# CE842170260_SHEET3.net
KiCad netlist of a schematic drawn in Altium Designer
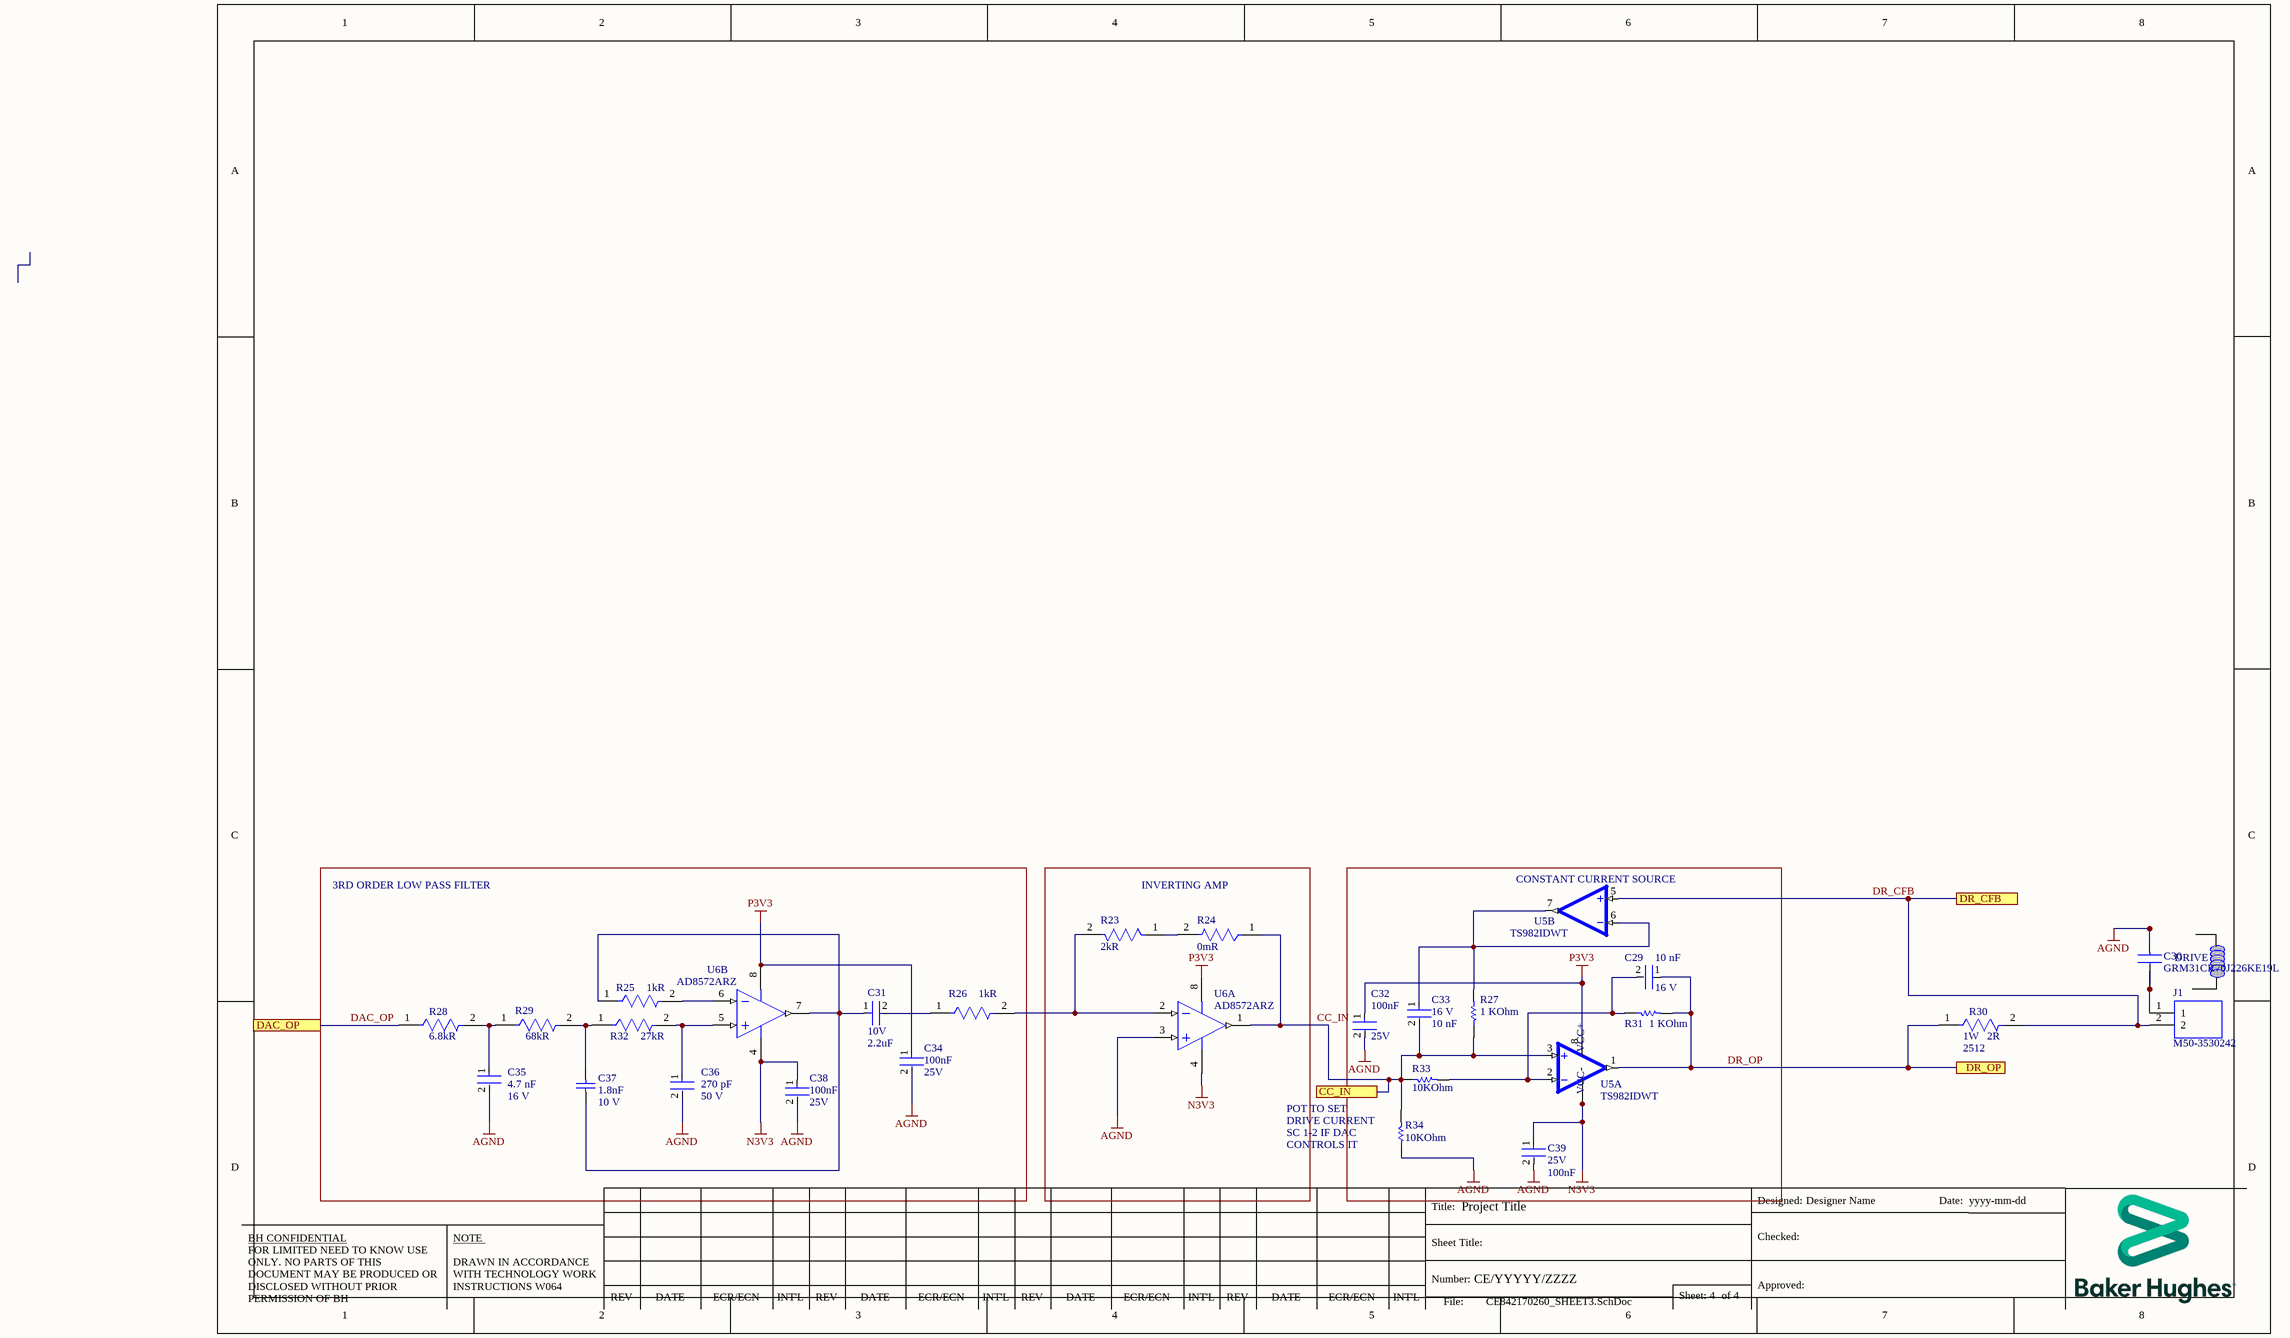
[diagram p0: CE842170260_SHEET3.SchDoc]

(export (version "E")
  (design (tool "Eeschema 10.0.6"))
  (components
    (comp (ref "C29")
      (value "CC0402KRX7R7BB103")
      (footprint "FP-CC0402-MFG")
      (description "CAP CER 10000PF 16V X7R 0402")
      (fields
        (field (name "CAPACITANCE") "10 nF")
        (field (name "TOLERANCE") "0.1")
        (field (name "VOLTAGE RATING") "16 V")
        (field (name "MANUFACTURER") "YAGEO")
      )
      (libsource (lib "Altium Content Vault") (part "11868f565c42a9108669ba33697ecf6"))
    )
    (comp (ref "C30")
      (value "GRM31CR70J226KE19L")
      (footprint "CAPC3216X180N")
      (description "Murata 1206 GRM 22uF Ceramic Multilayer Capacitor, 6.3 V dc, +125C, X7R Dielectric, +/-10% SMD")
      (fields (field (name "MOUSER PART NUMBER") "81-GRM31CR70J226KE9L"))
      (libsource (lib "GRM31CR70J226KE19L") (part "GRM31CR70J226KE19L"))
    )
    (comp (ref "C31")
      (value "CGB3B3X5R1A225M055AB")
      (footprint "FP-CGB3B-IPC_A")
      (description "Multilayer Ceramic Capacitors 2.2uF ±20% 10V X5R SMD 0603")
      (fields
        (field (name "VOLTAGE RATING") "10V")
        (field (name "TOLERANCE") "20%")
        (field (name "CAPACITANCE") "2.2uF")
      )
      (libsource (lib "Altium Content Vault") (part "b4654b650e69147ec39a6b967a45e02"))
    )
    (comp (ref "C32")
      (value "C1005X5R1E104K050BC")
      (footprint "FP-C1005-050-0_05-MFG")
      (description "Multilayer Ceramic Capacitors 100nF ±10% 25V X5R SMD 0402")
      (fields
        (field (name "VOLTAGE RATING (DC)") "25V")
        (field (name "CAPACITANCE") "100nF")
        (field (name "TOLERANCE") "10%")
        (field (name "VOLTAGE") "25V")
      )
      (libsource (lib "Altium Content Vault") (part "b4654b650e69147ec39a6b967a45e02"))
    )
    (comp (ref "C33")
      (value "CC0402KRX7R7BB103")
      (footprint "FP-CC0402-MFG")
      (description "CAP CER 10000PF 16V X7R 0402")
      (fields
        (field (name "CAPACITANCE") "10 nF")
        (field (name "TOLERANCE") "0.1")
        (field (name "VOLTAGE RATING") "16 V")
        (field (name "MANUFACTURER") "YAGEO")
      )
      (libsource (lib "Altium Content Vault") (part "11868f565c42a9108669ba33697ecf6"))
    )
    (comp (ref "C34")
      (value "C1005X5R1E104K050BC")
      (footprint "FP-C1005-050-0_05-MFG")
      (description "Multilayer Ceramic Capacitors 100nF ±10% 25V X5R SMD 0402")
      (fields
        (field (name "VOLTAGE RATING (DC)") "25V")
        (field (name "CAPACITANCE") "100nF")
        (field (name "TOLERANCE") "10%")
        (field (name "VOLTAGE") "25V")
      )
      (libsource (lib "Altium Content Vault") (part "b4654b650e69147ec39a6b967a45e02"))
    )
    (comp (ref "C35")
      (value "CC0402KRX7R7BB472")
      (footprint "FP-CC0402-MFG")
      (description "CAP CER 4700PF 16V X7R 0402")
      (fields
        (field (name "CAPACITANCE") "4.7 nF")
        (field (name "OCTOPART") "https://octopart.com/cc0402krx7r7bb472-yageo-44648962")
        (field (name "MANUFACTURER") "YAGEO")
        (field (name "VOLTAGE RATING") "16 V")
      )
      (libsource (lib "Altium Content Vault") (part "11868f565c42a9108669ba33697ecf6"))
    )
    (comp (ref "C36")
      (value "C0402C271K5RACTU")
      (footprint "FP-C0402-BB-MFG")
      (description "CAP CER 270PF 50V 10% X7R 0402")
      (fields
        (field (name "CAPACITANCE") "270 pF")
        (field (name "VOLTAGE RATING") "50 V")
        (field (name "MANUFACTURER") "Kemet")
        (field (name "OCTOPART") "https://octopart.com/c0402c271k5ractu-kemet-5510096")
      )
      (libsource (lib "Altium Content Vault") (part "b4654b650e69147ec39a6b967a45e02"))
    )
    (comp (ref "C37")
      (value "1.8nF")
      (footprint "CAPC0402(1005)60_N")
      (description "CAP 1.8nF 10V ±5% 0402 (1005 Metric) Thickness 0.6mm SMD")
      (fields
        (field (name "RATED VOLTAGE") "10 V")
        (field (name "TOLERANCE") "Â±5%")
        (field (name "Comment") "CAP 1.8nF 10V 0402(1005)")
      )
      (libsource (lib "Altium Content Vault") (part "CAP"))
    )
    (comp (ref "C38")
      (value "C1005X5R1E104K050BC")
      (footprint "FP-C1005-050-0_05-MFG")
      (description "Multilayer Ceramic Capacitors 100nF ±10% 25V X5R SMD 0402")
      (fields
        (field (name "VOLTAGE RATING (DC)") "25V")
        (field (name "CAPACITANCE") "100nF")
        (field (name "TOLERANCE") "10%")
        (field (name "VOLTAGE") "25V")
      )
      (libsource (lib "Altium Content Vault") (part "b4654b650e69147ec39a6b967a45e02"))
    )
    (comp (ref "C39")
      (value "C1005X5R1E104K050BC")
      (footprint "FP-C1005-050-0_05-MFG")
      (description "Multilayer Ceramic Capacitors 100nF ±10% 25V X5R SMD 0402")
      (fields
        (field (name "VOLTAGE RATING (DC)") "25V")
        (field (name "CAPACITANCE") "100nF")
        (field (name "TOLERANCE") "10%")
        (field (name "VOLTAGE") "25V")
      )
      (libsource (lib "Altium Content Vault") (part "b4654b650e69147ec39a6b967a45e02"))
    )
    (comp (ref "J1")
      (value "M50-3530242")
      (footprint "HDRV2W40P0X127_1X2_254X210X420P")
      (description "Headers & Wire Housings 2 WAY SIL VERT PC TAIL P/HDR")
      (fields (field (name "MOUSER PART NUMBER") "855-M50-3530242"))
      (libsource (lib "M50-3530242") (part "M50-3530242"))
    )
    (comp (ref "R23")
      (value "CRCW04022K00FKED")
      (footprint "FP-CRCW0402-e3-IPC_C")
      (description "RES Thick Film, 2kΩ, 1%, 0.063W, 100ppm/°C, 0402")
      (fields (field (name "TOLERANCE") "1%") (field (name "RESISTANCE") "2kR"))
      (libsource (lib "Altium Content Vault") (part "1029c3af85768c4190bb7ad29bc67b5"))
    )
    (comp (ref "R24")
      (value "MCS04020Z0000ZE000")
      (footprint "FP-MCS0402-MFG")
      (description "RES SMD 1.2K OHM 1% 1/10W 0402")
      (fields (field (name "RESISTANCE") "0mR"))
      (libsource (lib "Altium Content Vault") (part "1029c3af85768c4190bb7ad29bc67b5"))
    )
    (comp (ref "R25")
      (value "CRCW04021K00FKED")
      (footprint "FP-CRCW0402-e3-MFG")
      (description "RES Thick Film, 1kΩ, 1%, 0.063W, 100ppm/°C, 0402")
      (fields (field (name "RESISTANCE") "1kR") (field (name "TOLERANCE") "1%"))
      (libsource (lib "Altium Content Vault") (part "1029c3af85768c4190bb7ad29bc67b5"))
    )
    (comp (ref "R26")
      (value "CRCW04021K00FKED")
      (footprint "FP-CRCW0402-e3-MFG")
      (description "RES Thick Film, 1kΩ, 1%, 0.063W, 100ppm/°C, 0402")
      (fields (field (name "RESISTANCE") "1kR") (field (name "TOLERANCE") "1%"))
      (libsource (lib "Altium Content Vault") (part "1029c3af85768c4190bb7ad29bc67b5"))
    )
    (comp (ref "R27")
      (value "ERJ-2RKF1001X")
      (footprint "RESC1005X40X25NL05T05")
      (description "Chip Resistor, 1 KOhm, +/- 1%, 100 mW, -55 to 155 degC, 0402 (1005 Metric), RoHS, Tape and Reel")
      (fields
        (field (name "MANUFACTURER") "Basic Passives")
        (field (name "TOLERANCE") "1%")
        (field (name "RESISTANCE") "1 KOhm")
      )
      (libsource (lib "Altium Content Vault") (part "RES-2"))
    )
    (comp (ref "R28")
      (value "ERJ-2RKF6801X")
      (footprint "FP-ERJ2RK-IPC_B")
      (description "RES SMD 6.8K OHM 1% 1/10W 0402")
      (fields (field (name "RESISTANCE") "6.8kR") (field (name "TOLERANCE") "1%"))
      (libsource (lib "Altium Content Vault") (part "1029c3af85768c4190bb7ad29bc67b5"))
    )
    (comp (ref "R29")
      (value "CRCW040268K0JNED")
      (footprint "FP-CRCW0402-e3-IPC_C")
      (description "RES Thick Film, 68kΩ, 5%, 0.063W, 200ppm/°C, 0402")
      (fields (field (name "TOLERANCE") "5%") (field (name "RESISTANCE") "68kR"))
      (libsource (lib "Altium Content Vault") (part "1029c3af85768c4190bb7ad29bc67b5"))
    )
    (comp (ref "R30")
      (value "CRCW25122R00FNEG")
      (footprint "FP-CRCW2512-e3-IPC_A")
      (description "RES Thick Film, 2Ω, 1%, 1W, 200ppm/°C, 2512")
      (fields
        (field (name "CASE CODE (IMPERIAL)") "2512")
        (field (name "TOLERANCE") "1%")
        (field (name "RESISTANCE") "2R")
        (field (name "POWER RATING") "1W")
      )
      (libsource (lib "Altium Content Vault") (part "1029c3af85768c4190bb7ad29bc67b5"))
    )
    (comp (ref "R31")
      (value "ERJ-2RKF1001X")
      (footprint "RESC1005X40X25NL05T05")
      (description "Chip Resistor, 1 KOhm, +/- 1%, 100 mW, -55 to 155 degC, 0402 (1005 Metric), RoHS, Tape and Reel")
      (fields
        (field (name "MANUFACTURER") "Basic Passives")
        (field (name "TOLERANCE") "1%")
        (field (name "RESISTANCE") "1 KOhm")
      )
      (libsource (lib "Altium Content Vault") (part "RES-2"))
    )
    (comp (ref "R32")
      (value "CRCW040227K0JNED")
      (footprint "FP-CRCW0402-e3-IPC_C")
      (description "RES Thick Film, 27kΩ, 5%, 0.063W, 200ppm/°C, 0402")
      (fields (field (name "RESISTANCE") "27kR") (field (name "TOLERANCE") "5%"))
      (libsource (lib "Altium Content Vault") (part "1029c3af85768c4190bb7ad29bc67b5"))
    )
    (comp (ref "R33")
      (value "ERJ2RKF1002X")
      (footprint "RESC1005X40X25LL05T05")
      (description "Chip Resistor, 10 KOhm, +/- 1%, 0.1 W, -55 to 155 degC, 0402 (1005 Metric), RoHS, Tape and Reel")
      (fields
        (field (name "RESISTANCE") "10KOhm")
        (field (name "TOLERANCE") "1%")
        (field (name "MANUFACTURER") "Panasonic")
      )
      (libsource (lib "Altium Content Vault") (part "RES-2"))
    )
    (comp (ref "R34")
      (value "ERJ2RKF1002X")
      (footprint "RESC1005X40X25LL05T05")
      (description "Chip Resistor, 10 KOhm, +/- 1%, 0.1 W, -55 to 155 degC, 0402 (1005 Metric), RoHS, Tape and Reel")
      (fields
        (field (name "RESISTANCE") "10KOhm")
        (field (name "TOLERANCE") "1%")
        (field (name "MANUFACTURER") "Panasonic")
      )
      (libsource (lib "Altium Content Vault") (part "RES-2"))
    )
    (comp (ref "U5")
      (value "TS982IDWT")
      (footprint "SOIC127P600X175-9N")
      (libsource (lib "TS982IDWT") (part "TS982IDWT"))
    )
    (comp (ref "U6")
      (value "AD8572ARZ")
      (footprint "ADI-R-8_M")
      (fields (field (name "MANUFACTURER") "Analog Devices") (field (name "GENERIC PART NUMBER") "AD8572"))
      (libsource (lib "Altium Content Vault") (part "ADI-OP29X-R-8"))
    )
  )
  (nets
    (net (code "1") (name "/CC_IN") (class "Default")
      (node (ref "C33") (pin "2") (pinfunction "2_2") (pintype "passive"))
      (node (ref "R24") (pin "1") (pinfunction "1_1") (pintype "passive"))
      (node (ref "R27") (pin "1") (pinfunction "1_1") (pintype "passive"))
      (node (ref "R33") (pin "1") (pinfunction "1_1") (pintype "passive"))
      (node (ref "R34") (pin "2") (pinfunction "2_2") (pintype "passive"))
      (node (ref "U5") (pin "3") (pinfunction "NON_INVERTING_INPUT_1_3") (pintype "input"))
      (node (ref "U6") (pin "1") (pinfunction "OUT_A_1") (pintype "output"))
    )
    (net (code "2") (name "/DAC_OP") (class "Default")
      (node (ref "R28") (pin "1") (pinfunction "1_1") (pintype "passive"))
    )
    (net (code "3") (name "/DR_CFB") (class "Default")
      (node (ref "J1") (pin "2") (pinfunction "2_2") (pintype "passive"))
      (node (ref "R30") (pin "2") (pinfunction "2_2") (pintype "passive"))
      (node (ref "U5") (pin "5") (pinfunction "NON_INVERTING_INPUT_2_5") (pintype "input"))
    )
    (net (code "4") (name "/DR_OP") (class "Default")
      (node (ref "C29") (pin "1") (pinfunction "1_1") (pintype "passive"))
      (node (ref "R30") (pin "1") (pinfunction "1_1") (pintype "passive"))
      (node (ref "R31") (pin "2") (pinfunction "2_2") (pintype "passive"))
      (node (ref "U5") (pin "1") (pinfunction "OUTPUT1_1") (pintype "output"))
    )
    (net (code "5") (name "AGND") (class "Default")
      (node (ref "C30") (pin "2") (pinfunction "2_2") (pintype "passive"))
      (node (ref "C32") (pin "2") (pinfunction "2_2") (pintype "passive"))
      (node (ref "C34") (pin "2") (pinfunction "2_2") (pintype "passive"))
      (node (ref "C35") (pin "2") (pinfunction "2_2") (pintype "passive"))
      (node (ref "C36") (pin "2") (pinfunction "2_2") (pintype "passive"))
      (node (ref "C38") (pin "2") (pinfunction "2_2") (pintype "passive"))
      (node (ref "C39") (pin "2") (pinfunction "2_2") (pintype "passive"))
      (node (ref "R34") (pin "1") (pinfunction "1_1") (pintype "passive"))
      (node (ref "U6") (pin "3") (pinfunction "+IN_A_3") (pintype "input"))
    )
    (net (code "6") (name "N3V3") (class "Default")
      (node (ref "C38") (pin "1") (pinfunction "1_1") (pintype "passive"))
      (node (ref "C39") (pin "1") (pinfunction "1_1") (pintype "passive"))
      (node (ref "U5") (pin "4") (pinfunction "VCC-_4") (pintype "power_in"))
      (node (ref "U5") (pin "9") (pinfunction "VCC-_9") (pintype "power_in"))
      (node (ref "U6") (pin "4") (pinfunction "-V_4") (pintype "power_in"))
    )
    (net (code "7") (name "Net-(C30-Pad1)") (class "Default")
      (node (ref "C30") (pin "1") (pinfunction "1_1") (pintype "passive"))
      (node (ref "J1") (pin "1") (pinfunction "1_1") (pintype "passive"))
    )
    (net (code "8") (name "Net-(C31-Pad2)") (class "Default")
      (node (ref "C31") (pin "2") (pinfunction "2_2") (pintype "passive"))
      (node (ref "R26") (pin "1") (pinfunction "1_1") (pintype "passive"))
    )
    (net (code "9") (name "Net-(C35-Pad1)") (class "Default")
      (node (ref "C35") (pin "1") (pinfunction "1_1") (pintype "passive"))
      (node (ref "R28") (pin "2") (pinfunction "2_2") (pintype "passive"))
      (node (ref "R29") (pin "1") (pinfunction "1_1") (pintype "passive"))
    )
    (net (code "10") (name "Net-(C37-Pad2)") (class "Default")
      (node (ref "C37") (pin "2") (pinfunction "2_2") (pintype "passive"))
      (node (ref "R29") (pin "2") (pinfunction "2_2") (pintype "passive"))
      (node (ref "R32") (pin "1") (pinfunction "1_1") (pintype "passive"))
    )
    (net (code "11") (name "Net-(R23-Pad1)") (class "Default")
      (node (ref "R23") (pin "1") (pinfunction "1_1") (pintype "passive"))
      (node (ref "R24") (pin "2") (pinfunction "2_2") (pintype "passive"))
    )
    (net (code "12") (name "Net-(U5A-INVERTING_INPUT_1)") (class "Default")
      (node (ref "C29") (pin "2") (pinfunction "2_2") (pintype "passive"))
      (node (ref "R31") (pin "1") (pinfunction "1_1") (pintype "passive"))
      (node (ref "R33") (pin "2") (pinfunction "2_2") (pintype "passive"))
      (node (ref "U5") (pin "2") (pinfunction "INVERTING_INPUT_1_2") (pintype "input"))
    )
    (net (code "13") (name "Net-(U5B-INVERTING_INPUT_2)") (class "Default")
      (node (ref "C33") (pin "1") (pinfunction "1_1") (pintype "passive"))
      (node (ref "R27") (pin "2") (pinfunction "2_2") (pintype "passive"))
      (node (ref "U5") (pin "6") (pinfunction "INVERTING_INPUT_2_6") (pintype "input"))
      (node (ref "U5") (pin "7") (pinfunction "OUTPUT2_7") (pintype "output"))
    )
    (net (code "14") (name "Net-(U6A--IN_A)") (class "Default")
      (node (ref "R23") (pin "2") (pinfunction "2_2") (pintype "passive"))
      (node (ref "R26") (pin "2") (pinfunction "2_2") (pintype "passive"))
      (node (ref "U6") (pin "2") (pinfunction "-IN_A_2") (pintype "input"))
    )
    (net (code "15") (name "Net-(U6B-+IN_B)") (class "Default")
      (node (ref "C36") (pin "1") (pinfunction "1_1") (pintype "passive"))
      (node (ref "R32") (pin "2") (pinfunction "2_2") (pintype "passive"))
      (node (ref "U6") (pin "5") (pinfunction "+IN_B_5") (pintype "input"))
    )
    (net (code "16") (name "Net-(U6B--IN_B)") (class "Default")
      (node (ref "R25") (pin "2") (pinfunction "2_2") (pintype "passive"))
      (node (ref "U6") (pin "6") (pinfunction "-IN_B_6") (pintype "input"))
    )
    (net (code "17") (name "Net-(U6B-OUT_B)") (class "Default")
      (node (ref "C31") (pin "1") (pinfunction "1_1") (pintype "passive"))
      (node (ref "C37") (pin "1") (pinfunction "1_1") (pintype "passive"))
      (node (ref "R25") (pin "1") (pinfunction "1_1") (pintype "passive"))
      (node (ref "U6") (pin "7") (pinfunction "OUT_B_7") (pintype "output"))
    )
    (net (code "18") (name "P3V3") (class "Default")
      (node (ref "C32") (pin "1") (pinfunction "1_1") (pintype "passive"))
      (node (ref "C34") (pin "1") (pinfunction "1_1") (pintype "passive"))
      (node (ref "U5") (pin "8") (pinfunction "VCC+_8") (pintype "power_in"))
      (node (ref "U6") (pin "8") (pinfunction "+V_8") (pintype "power_in"))
    )
  )
)
